# power1pDINline4.net
KiCad netlist of a schematic drawn in EAGLE
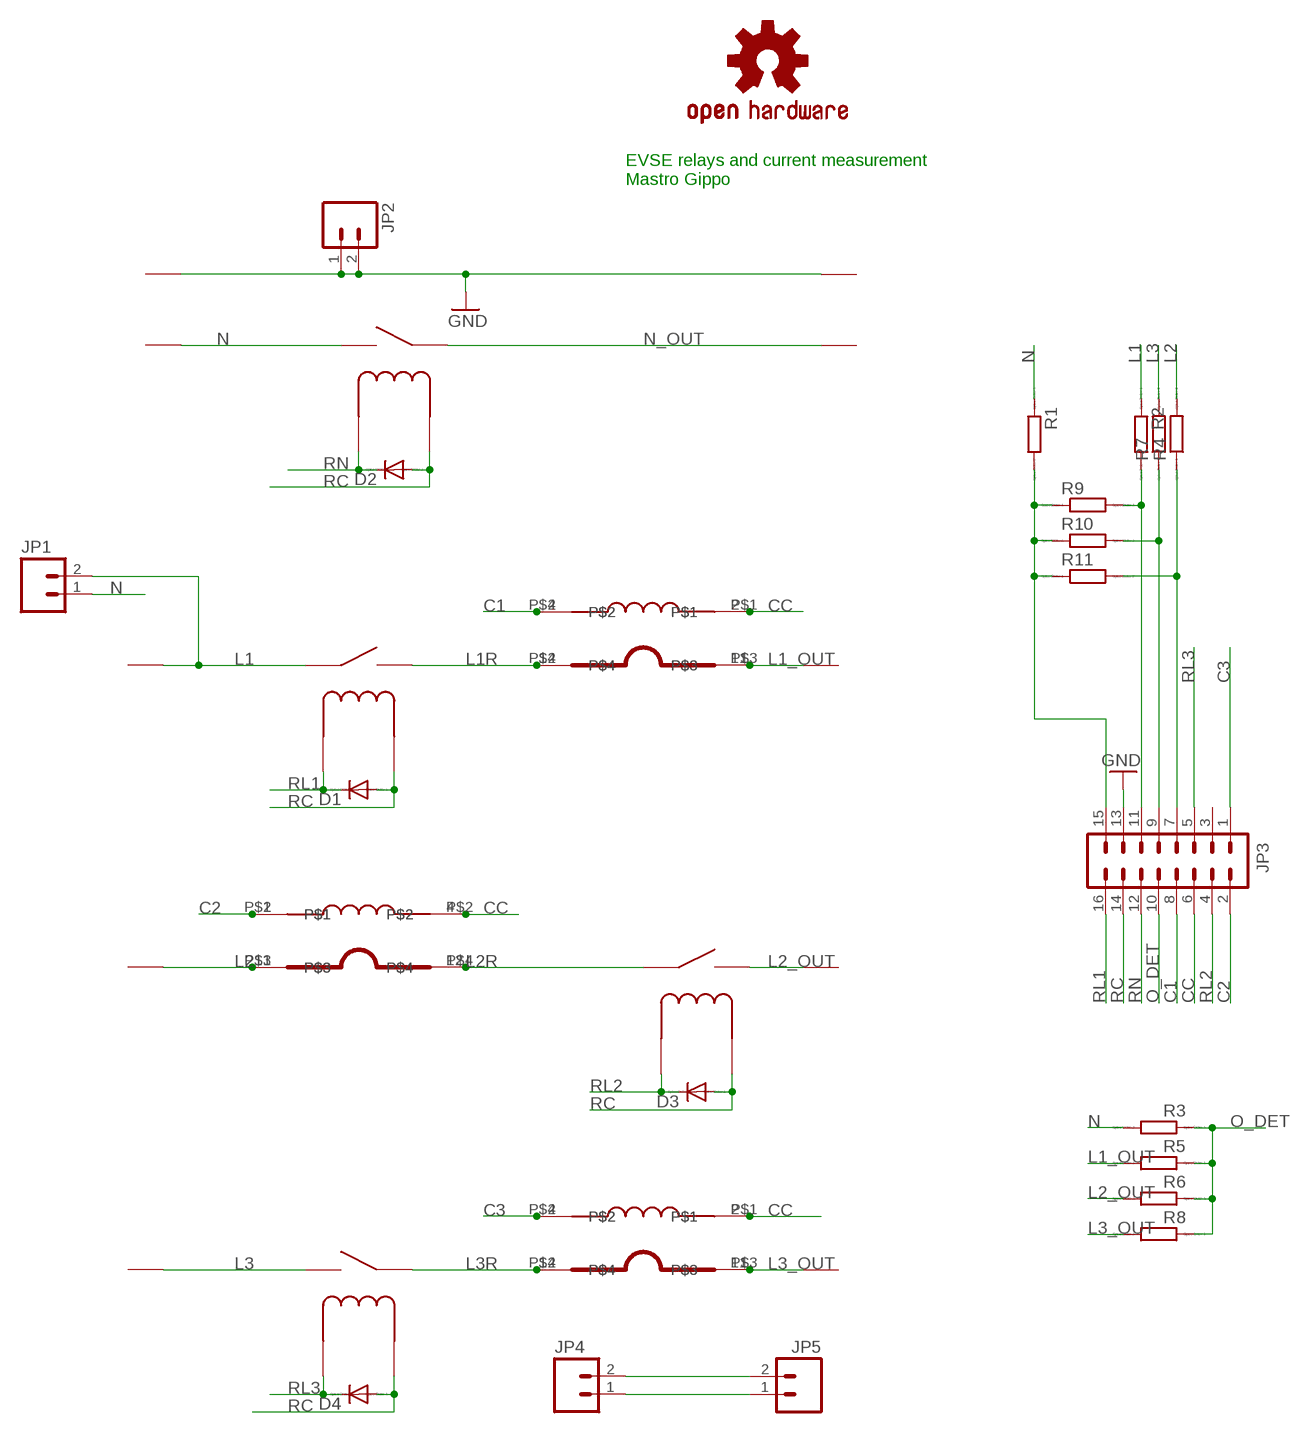
[diagram p0: schematic, sheet 1]

(export (version "E")
  (design (tool "Eeschema 10.0.6"))
  (components
    (comp (ref "D1")
      (value "DIODE-DO-214AC")
      (footprint "eagle-import:DO-214AC")
      (libsource (lib "eagle-import") (part "DIODE-DO-214AC"))
    )
    (comp (ref "D2")
      (value "DIODE-DO-214AC")
      (footprint "eagle-import:DO-214AC")
      (libsource (lib "eagle-import") (part "DIODE-DO-214AC"))
    )
    (comp (ref "D3")
      (value "DIODE-DO-214AC")
      (footprint "eagle-import:DO-214AC")
      (libsource (lib "eagle-import") (part "DIODE-DO-214AC"))
    )
    (comp (ref "D4")
      (value "DIODE-DO-214AC")
      (footprint "eagle-import:DO-214AC")
      (libsource (lib "eagle-import") (part "DIODE-DO-214AC"))
    )
    (comp (ref "JP1")
      (value "M025MM")
      (footprint "eagle-import:SCREWTERMINAL-5MM-2")
      (libsource (lib "eagle-import") (part "M025MM"))
    )
    (comp (ref "JP2")
      (value "M025MM")
      (footprint "eagle-import:SCREWTERMINAL-5MM-2")
      (libsource (lib "eagle-import") (part "M025MM"))
    )
    (comp (ref "JP3")
      (value "M08X2")
      (footprint "eagle-import:2X8")
      (libsource (lib "eagle-import") (part "M08X2"))
    )
    (comp (ref "JP4")
      (value "M025MM")
      (footprint "eagle-import:SCREWTERMINAL-5MM-2")
      (libsource (lib "eagle-import") (part "M025MM"))
    )
    (comp (ref "JP5")
      (value "M025MM")
      (footprint "eagle-import:SCREWTERMINAL-5MM-2")
      (libsource (lib "eagle-import") (part "M025MM"))
    )
    (comp (ref "R1")
      (value "R-EU_0207_10")
      (footprint "eagle-import:0207_10")
      (libsource (lib "eagle-import") (part "R-EU_0207_10"))
    )
    (comp (ref "R2")
      (value "R-EU_0207_10")
      (footprint "eagle-import:0207_10")
      (libsource (lib "eagle-import") (part "R-EU_0207_10"))
    )
    (comp (ref "R3")
      (value "R-EU_0207_10")
      (footprint "eagle-import:0207_10")
      (libsource (lib "eagle-import") (part "R-EU_0207_10"))
    )
    (comp (ref "R4")
      (value "R-EU_0207_10")
      (footprint "eagle-import:0207_10")
      (libsource (lib "eagle-import") (part "R-EU_0207_10"))
    )
    (comp (ref "R5")
      (value "R-EU_0207_10")
      (footprint "eagle-import:0207_10")
      (libsource (lib "eagle-import") (part "R-EU_0207_10"))
    )
    (comp (ref "R6")
      (value "R-EU_0207_10")
      (footprint "eagle-import:0207_10")
      (libsource (lib "eagle-import") (part "R-EU_0207_10"))
    )
    (comp (ref "R7")
      (value "R-EU_0207_10")
      (footprint "eagle-import:0207_10")
      (libsource (lib "eagle-import") (part "R-EU_0207_10"))
    )
    (comp (ref "R8")
      (value "R-EU_0207_10")
      (footprint "eagle-import:0207_10")
      (libsource (lib "eagle-import") (part "R-EU_0207_10"))
    )
    (comp (ref "R9")
      (value "R-EU_M0805")
      (footprint "eagle-import:M0805")
      (libsource (lib "eagle-import") (part "R-EU_M0805"))
    )
    (comp (ref "R10")
      (value "R-EU_M0805")
      (footprint "eagle-import:M0805")
      (libsource (lib "eagle-import") (part "R-EU_M0805"))
    )
    (comp (ref "R11")
      (value "R-EU_M0805")
      (footprint "eagle-import:M0805")
      (libsource (lib "eagle-import") (part "R-EU_M0805"))
    )
    (comp (ref "U$1")
      (value "T9S")
      (footprint "eagle-import:T9SSOLAR")
      (libsource (lib "eagle-import") (part "T9S"))
    )
    (comp (ref "U$2")
      (value "T9S")
      (footprint "eagle-import:T9SSOLAR")
      (libsource (lib "eagle-import") (part "T9S"))
    )
    (comp (ref "U$3")
      (value "PLH5_1")
      (footprint "eagle-import:PLH5")
      (libsource (lib "eagle-import") (part "PLH5_1"))
    )
    (comp (ref "U$4")
      (value "PLH5_1")
      (footprint "eagle-import:PLH5")
      (libsource (lib "eagle-import") (part "PLH5_1"))
    )
    (comp (ref "U$5")
      (value "PLH5_1")
      (footprint "eagle-import:PLH5")
      (libsource (lib "eagle-import") (part "PLH5_1"))
    )
    (comp (ref "U$6")
      (value "PLH5_1")
      (footprint "eagle-import:PLH5")
      (libsource (lib "eagle-import") (part "PLH5_1"))
    )
    (comp (ref "U$7")
      (value "PLH5_1")
      (footprint "eagle-import:PLH5")
      (libsource (lib "eagle-import") (part "PLH5_1"))
    )
    (comp (ref "U$8")
      (value "CSE187L")
      (footprint "eagle-import:CSE187L")
      (libsource (lib "eagle-import") (part "CSE187L"))
    )
    (comp (ref "U$9")
      (value "PLH5_1")
      (footprint "eagle-import:PLH5")
      (libsource (lib "eagle-import") (part "PLH5_1"))
    )
    (comp (ref "U$10")
      (value "PLH5_1")
      (footprint "eagle-import:PLH5")
      (libsource (lib "eagle-import") (part "PLH5_1"))
    )
    (comp (ref "U$11")
      (value "PLH5_1")
      (footprint "eagle-import:PLH5")
      (libsource (lib "eagle-import") (part "PLH5_1"))
    )
    (comp (ref "U$12")
      (value "T9S")
      (footprint "eagle-import:T9SSOLAR")
      (libsource (lib "eagle-import") (part "T9S"))
    )
    (comp (ref "U$14")
      (value "PLH5_1")
      (footprint "eagle-import:PLH5")
      (libsource (lib "eagle-import") (part "PLH5_1"))
    )
    (comp (ref "U$15")
      (value "PLH5_1")
      (footprint "eagle-import:PLH5")
      (libsource (lib "eagle-import") (part "PLH5_1"))
    )
    (comp (ref "U$16")
      (value "PB0025NL")
      (footprint "eagle-import:PILSA_CURR_MIN")
      (libsource (lib "eagle-import") (part "PB0025NL"))
    )
    (comp (ref "U$17")
      (value "T9S")
      (footprint "eagle-import:T9SSOLAR")
      (libsource (lib "eagle-import") (part "T9S"))
    )
    (comp (ref "U$18")
      (value "PB0025NL")
      (footprint "eagle-import:PILSA_CURR_MIN")
      (libsource (lib "eagle-import") (part "PB0025NL"))
    )
    (comp (ref "U$19")
      (value "PB0025NL")
      (footprint "eagle-import:PILSA_CURR_MIN")
      (libsource (lib "eagle-import") (part "PB0025NL"))
    )
    (comp (ref "U$20")
      (value "CSE187L")
      (footprint "eagle-import:CSE187L")
      (libsource (lib "eagle-import") (part "CSE187L"))
    )
    (comp (ref "U$21")
      (value "OSHW-LOGOL")
      (footprint "eagle-import:OSHW-LOGO-L")
      (libsource (lib "eagle-import") (part "OSHW-LOGOL"))
    )
    (comp (ref "U$22")
      (value "CSE187L")
      (footprint "eagle-import:CSE187L")
      (libsource (lib "eagle-import") (part "CSE187L"))
    )
  )
  (nets
    (net (code "1") (name "/C1") (class "Default")
      (node (ref "JP3") (pin "8") (pinfunction "8_8") (pintype "passive"))
      (node (ref "U$18") (pin "4") (pinfunction "P$2_4") (pintype "bidirectional"))
      (node (ref "U$8") (pin "P$2") (pinfunction "P$2_P$2") (pintype "bidirectional"))
    )
    (net (code "2") (name "/C2") (class "Default")
      (node (ref "JP3") (pin "2") (pinfunction "2_2") (pintype "passive"))
      (node (ref "U$19") (pin "2") (pinfunction "P$1_2") (pintype "bidirectional"))
      (node (ref "U$22") (pin "P$1") (pinfunction "P$1_P$1") (pintype "bidirectional"))
    )
    (net (code "3") (name "/C3") (class "Default")
      (node (ref "JP3") (pin "1") (pinfunction "1_1") (pintype "passive"))
      (node (ref "U$16") (pin "4") (pinfunction "P$2_4") (pintype "bidirectional"))
      (node (ref "U$20") (pin "P$2") (pinfunction "P$2_P$2") (pintype "bidirectional"))
    )
    (net (code "4") (name "/CC") (class "Default")
      (node (ref "JP3") (pin "6") (pinfunction "6_6") (pintype "passive"))
      (node (ref "U$16") (pin "2") (pinfunction "P$1_2") (pintype "bidirectional"))
      (node (ref "U$18") (pin "2") (pinfunction "P$1_2") (pintype "bidirectional"))
      (node (ref "U$19") (pin "4") (pinfunction "P$2_4") (pintype "bidirectional"))
      (node (ref "U$20") (pin "P$1") (pinfunction "P$1_P$1") (pintype "bidirectional"))
      (node (ref "U$22") (pin "P$2") (pinfunction "P$2_P$2") (pintype "bidirectional"))
      (node (ref "U$8") (pin "P$1") (pinfunction "P$1_P$1") (pintype "bidirectional"))
    )
    (net (code "5") (name "/L1") (class "Default")
      (node (ref "JP1") (pin "2") (pinfunction "2_2") (pintype "passive"))
      (node (ref "R2") (pin "1") (pinfunction "1_1") (pintype "passive"))
      (node (ref "U$2") (pin "TR1") (pinfunction "TR_TR1") (pintype "bidirectional"))
      (node (ref "U$2") (pin "TR2") (pinfunction "TR_TR2") (pintype "bidirectional"))
      (node (ref "U$4") (pin "P$1") (pinfunction "P$1_P$1") (pintype "bidirectional"))
      (node (ref "U$4") (pin "P$2") (pinfunction "P$1_P$2") (pintype "bidirectional"))
    )
    (net (code "6") (name "/L1R") (class "Default")
      (node (ref "U$18") (pin "12") (pinfunction "P$4_12") (pintype "bidirectional"))
      (node (ref "U$2") (pin "TL1") (pinfunction "TL_TL1") (pintype "bidirectional"))
      (node (ref "U$2") (pin "TL2") (pinfunction "TL_TL2") (pintype "bidirectional"))
      (node (ref "U$8") (pin "P$4") (pinfunction "P$4_P$4") (pintype "bidirectional"))
    )
    (net (code "7") (name "/L1_OUT") (class "Default")
      (node (ref "R5") (pin "2") (pinfunction "2_2") (pintype "passive"))
      (node (ref "U$18") (pin "11") (pinfunction "P$3_11") (pintype "bidirectional"))
      (node (ref "U$6") (pin "P$1") (pinfunction "P$1_P$1") (pintype "bidirectional"))
      (node (ref "U$6") (pin "P$2") (pinfunction "P$1_P$2") (pintype "bidirectional"))
      (node (ref "U$8") (pin "P$3") (pinfunction "P$3_P$3") (pintype "bidirectional"))
    )
    (net (code "8") (name "/L2") (class "Default")
      (node (ref "R4") (pin "2") (pinfunction "2_2") (pintype "passive"))
      (node (ref "U$19") (pin "11") (pinfunction "P$3_11") (pintype "bidirectional"))
      (node (ref "U$22") (pin "P$3") (pinfunction "P$3_P$3") (pintype "bidirectional"))
      (node (ref "U$7") (pin "P$1") (pinfunction "P$1_P$1") (pintype "bidirectional"))
      (node (ref "U$7") (pin "P$2") (pinfunction "P$1_P$2") (pintype "bidirectional"))
    )
    (net (code "9") (name "/L2R") (class "Default")
      (node (ref "U$12") (pin "TR1") (pinfunction "TR_TR1") (pintype "bidirectional"))
      (node (ref "U$12") (pin "TR2") (pinfunction "TR_TR2") (pintype "bidirectional"))
      (node (ref "U$19") (pin "12") (pinfunction "P$4_12") (pintype "bidirectional"))
      (node (ref "U$22") (pin "P$4") (pinfunction "P$4_P$4") (pintype "bidirectional"))
    )
    (net (code "10") (name "/L2_OUT") (class "Default")
      (node (ref "R6") (pin "2") (pinfunction "2_2") (pintype "passive"))
      (node (ref "U$11") (pin "P$1") (pinfunction "P$1_P$1") (pintype "bidirectional"))
      (node (ref "U$11") (pin "P$2") (pinfunction "P$1_P$2") (pintype "bidirectional"))
      (node (ref "U$12") (pin "TL1") (pinfunction "TL_TL1") (pintype "bidirectional"))
      (node (ref "U$12") (pin "TL2") (pinfunction "TL_TL2") (pintype "bidirectional"))
    )
    (net (code "11") (name "/L3") (class "Default")
      (node (ref "R7") (pin "2") (pinfunction "2_2") (pintype "passive"))
      (node (ref "U$14") (pin "P$1") (pinfunction "P$1_P$1") (pintype "bidirectional"))
      (node (ref "U$14") (pin "P$2") (pinfunction "P$1_P$2") (pintype "bidirectional"))
      (node (ref "U$17") (pin "TL1") (pinfunction "TL_TL1") (pintype "bidirectional"))
      (node (ref "U$17") (pin "TL2") (pinfunction "TL_TL2") (pintype "bidirectional"))
    )
    (net (code "12") (name "/L3R") (class "Default")
      (node (ref "U$16") (pin "12") (pinfunction "P$4_12") (pintype "bidirectional"))
      (node (ref "U$17") (pin "TR1") (pinfunction "TR_TR1") (pintype "bidirectional"))
      (node (ref "U$17") (pin "TR2") (pinfunction "TR_TR2") (pintype "bidirectional"))
      (node (ref "U$20") (pin "P$4") (pinfunction "P$4_P$4") (pintype "bidirectional"))
    )
    (net (code "13") (name "/L3_OUT") (class "Default")
      (node (ref "R8") (pin "2") (pinfunction "2_2") (pintype "passive"))
      (node (ref "U$15") (pin "P$1") (pinfunction "P$1_P$1") (pintype "bidirectional"))
      (node (ref "U$15") (pin "P$2") (pinfunction "P$1_P$2") (pintype "bidirectional"))
      (node (ref "U$16") (pin "11") (pinfunction "P$3_11") (pintype "bidirectional"))
      (node (ref "U$20") (pin "P$3") (pinfunction "P$3_P$3") (pintype "bidirectional"))
    )
    (net (code "14") (name "/N") (class "Default")
      (node (ref "JP1") (pin "1") (pinfunction "1_1") (pintype "passive"))
      (node (ref "R1") (pin "1") (pinfunction "1_1") (pintype "passive"))
      (node (ref "R3") (pin "2") (pinfunction "2_2") (pintype "passive"))
      (node (ref "U$1") (pin "TL1") (pinfunction "TL_TL1") (pintype "bidirectional"))
      (node (ref "U$1") (pin "TL2") (pinfunction "TL_TL2") (pintype "bidirectional"))
      (node (ref "U$3") (pin "P$1") (pinfunction "P$1_P$1") (pintype "bidirectional"))
      (node (ref "U$3") (pin "P$2") (pinfunction "P$1_P$2") (pintype "bidirectional"))
    )
    (net (code "15") (name "/N_OUT") (class "Default")
      (node (ref "U$1") (pin "TR1") (pinfunction "TR_TR1") (pintype "bidirectional"))
      (node (ref "U$1") (pin "TR2") (pinfunction "TR_TR2") (pintype "bidirectional"))
      (node (ref "U$5") (pin "P$1") (pinfunction "P$1_P$1") (pintype "bidirectional"))
      (node (ref "U$5") (pin "P$2") (pinfunction "P$1_P$2") (pintype "bidirectional"))
    )
    (net (code "16") (name "/O_DET") (class "Default")
      (node (ref "JP3") (pin "10") (pinfunction "10_10") (pintype "passive"))
      (node (ref "R3") (pin "1") (pinfunction "1_1") (pintype "passive"))
      (node (ref "R5") (pin "1") (pinfunction "1_1") (pintype "passive"))
      (node (ref "R6") (pin "1") (pinfunction "1_1") (pintype "passive"))
      (node (ref "R8") (pin "1") (pinfunction "1_1") (pintype "passive"))
    )
    (net (code "17") (name "/RC") (class "Default")
      (node (ref "D1") (pin "A") (pinfunction "A_A") (pintype "passive"))
      (node (ref "D2") (pin "A") (pinfunction "A_A") (pintype "passive"))
      (node (ref "D3") (pin "A") (pinfunction "A_A") (pintype "passive"))
      (node (ref "D4") (pin "A") (pinfunction "A_A") (pintype "passive"))
      (node (ref "JP3") (pin "14") (pinfunction "14_14") (pintype "passive"))
      (node (ref "U$1") (pin "C2") (pinfunction "C2_C2") (pintype "bidirectional"))
      (node (ref "U$12") (pin "C1") (pinfunction "C1_C1") (pintype "bidirectional"))
      (node (ref "U$17") (pin "C2") (pinfunction "C2_C2") (pintype "bidirectional"))
      (node (ref "U$2") (pin "C1") (pinfunction "C1_C1") (pintype "bidirectional"))
    )
    (net (code "18") (name "/RL1") (class "Default")
      (node (ref "D1") (pin "C") (pinfunction "C_C") (pintype "passive"))
      (node (ref "JP3") (pin "16") (pinfunction "16_16") (pintype "passive"))
      (node (ref "U$2") (pin "C2") (pinfunction "C2_C2") (pintype "bidirectional"))
    )
    (net (code "19") (name "/RL2") (class "Default")
      (node (ref "D3") (pin "C") (pinfunction "C_C") (pintype "passive"))
      (node (ref "JP3") (pin "4") (pinfunction "4_4") (pintype "passive"))
      (node (ref "U$12") (pin "C2") (pinfunction "C2_C2") (pintype "bidirectional"))
    )
    (net (code "20") (name "/RL3") (class "Default")
      (node (ref "D4") (pin "C") (pinfunction "C_C") (pintype "passive"))
      (node (ref "JP3") (pin "5") (pinfunction "5_5") (pintype "passive"))
      (node (ref "U$17") (pin "C1") (pinfunction "C1_C1") (pintype "bidirectional"))
    )
    (net (code "21") (name "/RN") (class "Default")
      (node (ref "D2") (pin "C") (pinfunction "C_C") (pintype "passive"))
      (node (ref "JP3") (pin "12") (pinfunction "12_12") (pintype "passive"))
      (node (ref "U$1") (pin "C1") (pinfunction "C1_C1") (pintype "bidirectional"))
    )
    (net (code "22") (name "GND") (class "Default")
      (node (ref "JP2") (pin "1") (pinfunction "1_1") (pintype "passive"))
      (node (ref "JP2") (pin "2") (pinfunction "2_2") (pintype "passive"))
      (node (ref "JP3") (pin "13") (pinfunction "13_13") (pintype "passive"))
      (node (ref "U$10") (pin "P$1") (pinfunction "P$1_P$1") (pintype "bidirectional"))
      (node (ref "U$10") (pin "P$2") (pinfunction "P$1_P$2") (pintype "bidirectional"))
      (node (ref "U$9") (pin "P$1") (pinfunction "P$1_P$1") (pintype "bidirectional"))
      (node (ref "U$9") (pin "P$2") (pinfunction "P$1_P$2") (pintype "bidirectional"))
    )
    (net (code "23") (name "Net-(JP3-Pad7)") (class "Default")
      (node (ref "JP3") (pin "7") (pinfunction "7_7") (pintype "passive"))
      (node (ref "R11") (pin "2") (pinfunction "2_2") (pintype "passive"))
      (node (ref "R4") (pin "1") (pinfunction "1_1") (pintype "passive"))
    )
    (net (code "24") (name "Net-(JP3-Pad9)") (class "Default")
      (node (ref "JP3") (pin "9") (pinfunction "9_9") (pintype "passive"))
      (node (ref "R10") (pin "2") (pinfunction "2_2") (pintype "passive"))
      (node (ref "R7") (pin "1") (pinfunction "1_1") (pintype "passive"))
    )
    (net (code "25") (name "Net-(JP3-Pad11)") (class "Default")
      (node (ref "JP3") (pin "11") (pinfunction "11_11") (pintype "passive"))
      (node (ref "R2") (pin "2") (pinfunction "2_2") (pintype "passive"))
      (node (ref "R9") (pin "2") (pinfunction "2_2") (pintype "passive"))
    )
    (net (code "26") (name "Net-(JP3-Pad15)") (class "Default")
      (node (ref "JP3") (pin "15") (pinfunction "15_15") (pintype "passive"))
      (node (ref "R1") (pin "2") (pinfunction "2_2") (pintype "passive"))
      (node (ref "R10") (pin "1") (pinfunction "1_1") (pintype "passive"))
      (node (ref "R11") (pin "1") (pinfunction "1_1") (pintype "passive"))
      (node (ref "R9") (pin "1") (pinfunction "1_1") (pintype "passive"))
    )
    (net (code "27") (name "Net-(JP4-Pad1)") (class "Default")
      (node (ref "JP4") (pin "1") (pinfunction "1_1") (pintype "passive"))
      (node (ref "JP5") (pin "1") (pinfunction "1_1") (pintype "passive"))
    )
    (net (code "28") (name "Net-(JP4-Pad2)") (class "Default")
      (node (ref "JP4") (pin "2") (pinfunction "2_2") (pintype "passive"))
      (node (ref "JP5") (pin "2") (pinfunction "2_2") (pintype "passive"))
    )
    (net (code "29") (name "unconnected-(JP3-Pad3)") (class "Default")
      (node (ref "JP3") (pin "3") (pinfunction "3_3") (pintype "passive"))
    )
  )
)
